# NBT_RTC_ADDON.net
KiCad netlist of a schematic drawn in Altium Designer
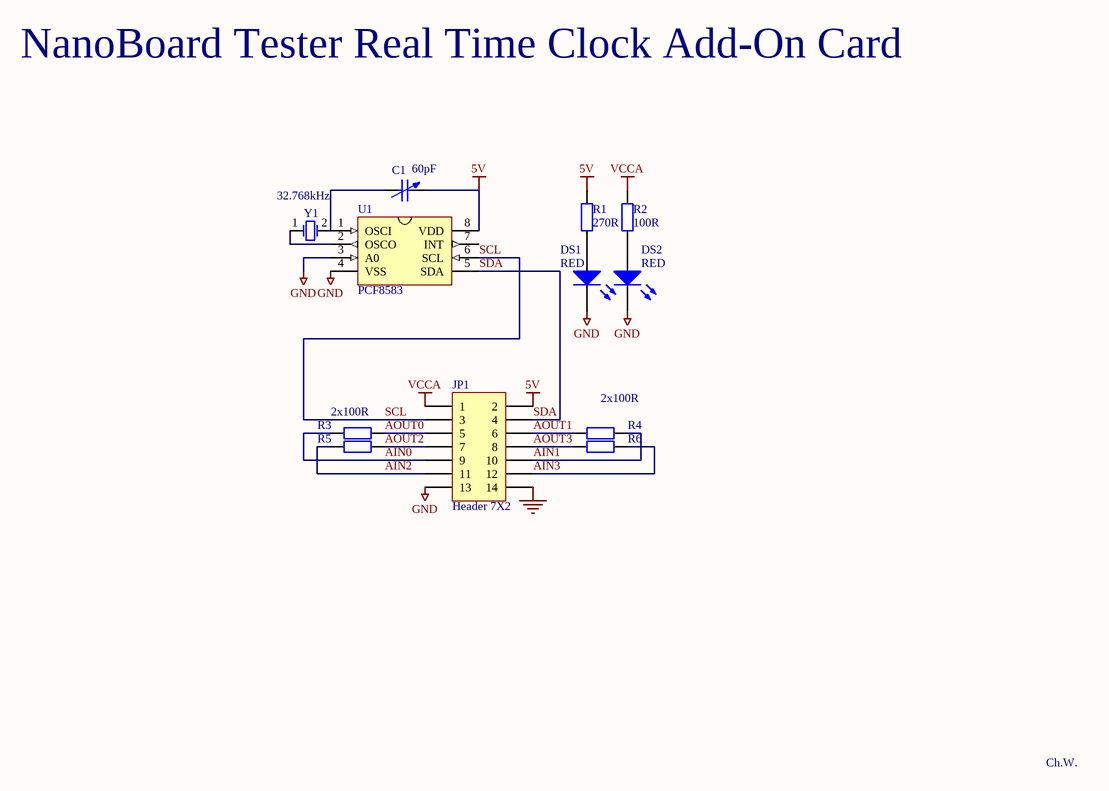
[diagram p0: NBT_RTC_ADDON.SchDoc]

(export (version "E")
  (design (tool "Eeschema 10.0.6"))
  (components
    (comp (ref "C1")
      (value "60pF")
      (footprint "C3225-1210")
      (description "Variable or Adjustable Capacitor")
      (fields
        (field (name "MANUFACTURER") "Generic Components")
        (field (name "Comment") "Cap Var")
        (field (name "PUBLISHER") "Altium Limited")
      )
      (libsource (lib "Miscellaneous Devices") (part "Cap Var"))
    )
    (comp (ref "DS1")
      (value "LED2")
      (footprint "DSO-F2/D6.1")
      (description "Typical RED, GREEN, YELLOW, AMBER GaAs LED")
      (fields
        (field (name "MANUFACTURER") "Generic Components")
        (field (name "ALTIUM_UNNAMED_1") "RED")
        (field (name "PUBLISHER") "Altium Limited")
      )
      (libsource (lib "Miscellaneous Devices") (part "LED2"))
    )
    (comp (ref "DS2")
      (value "LED2")
      (footprint "DSO-F2/D6.1")
      (description "Typical RED, GREEN, YELLOW, AMBER GaAs LED")
      (fields
        (field (name "MANUFACTURER") "Generic Components")
        (field (name "ALTIUM_UNNAMED_1") "RED")
        (field (name "PUBLISHER") "Altium Limited")
      )
      (libsource (lib "Miscellaneous Devices") (part "LED2"))
    )
    (comp (ref "JP1")
      (value "Header 7X2")
      (footprint "HDR2X7")
      (description "Header, 7-Pin, Dual row")
      (fields (field (name "MANUFACTURER") "Generic Components") (field (name "PUBLISHER") "Altium Limited"))
      (libsource (lib "Miscellaneous Connectors") (part "Header 7X2"))
    )
    (comp (ref "R1")
      (value "270R")
      (footprint "AXIAL-0.4")
      (description "Resistor")
      (fields (field (name "MANUFACTURER") "Generic Components") (field (name "PUBLISHER") "Altium Limited"))
      (libsource (lib "") (part "Res2_1"))
    )
    (comp (ref "R2")
      (value "100R")
      (footprint "AXIAL-0.4")
      (description "Resistor")
      (fields (field (name "MANUFACTURER") "Generic Components") (field (name "PUBLISHER") "Altium Limited"))
      (libsource (lib "") (part "Res2_1"))
    )
    (comp (ref "R3")
      (value "Res2")
      (footprint "AXIAL-0.4")
      (description "Resistor")
      (fields (field (name "MANUFACTURER") "Generic Components") (field (name "PUBLISHER") "Altium Limited"))
      (libsource (lib "Miscellaneous Devices") (part "Res2"))
    )
    (comp (ref "R4")
      (value "Res2")
      (footprint "AXIAL-0.4")
      (description "Resistor")
      (fields (field (name "MANUFACTURER") "Generic Components") (field (name "PUBLISHER") "Altium Limited"))
      (libsource (lib "Miscellaneous Devices") (part "Res2"))
    )
    (comp (ref "R5")
      (value "Res2")
      (footprint "AXIAL-0.4")
      (description "Resistor")
      (fields (field (name "MANUFACTURER") "Generic Components") (field (name "PUBLISHER") "Altium Limited"))
      (libsource (lib "Miscellaneous Devices") (part "Res2"))
    )
    (comp (ref "R6")
      (value "Res2")
      (footprint "AXIAL-0.4")
      (description "Resistor")
      (fields (field (name "MANUFACTURER") "Generic Components") (field (name "PUBLISHER") "Altium Limited"))
      (libsource (lib "Miscellaneous Devices") (part "Res2"))
    )
    (comp (ref "U1")
      (value "PCF8583")
      (footprint "DIP-8")
      (description "Clock/Calendar with 240 x 8-bit RAM")
      (libsource (lib "ChrisSchematic") (part "PCF8583"))
    )
    (comp (ref "Y1")
      (value "32.768kHz")
      (footprint "BCY-W2/D3.1")
      (description "Crystal Oscillator")
      (fields (field (name "MANUFACTURER") "Generic Components") (field (name "PUBLISHER") "Altium Limited"))
      (libsource (lib "Miscellaneous Devices") (part "XTAL"))
    )
  )
  (nets
    (net (code "1") (name "/AIN0") (class "Default")
      (node (ref "JP1") (pin "9") (pinfunction "9_9") (pintype "passive"))
      (node (ref "R3") (pin "2") (pinfunction "2_2") (pintype "passive"))
    )
    (net (code "2") (name "/AIN1") (class "Default")
      (node (ref "JP1") (pin "10") (pinfunction "10_10") (pintype "passive"))
      (node (ref "R4") (pin "1") (pinfunction "1_1") (pintype "passive"))
    )
    (net (code "3") (name "/AIN2") (class "Default")
      (node (ref "JP1") (pin "11") (pinfunction "11_11") (pintype "passive"))
      (node (ref "R5") (pin "2") (pinfunction "2_2") (pintype "passive"))
    )
    (net (code "4") (name "/AIN3") (class "Default")
      (node (ref "JP1") (pin "12") (pinfunction "12_12") (pintype "passive"))
      (node (ref "R6") (pin "1") (pinfunction "1_1") (pintype "passive"))
    )
    (net (code "5") (name "/AOUT0") (class "Default")
      (node (ref "JP1") (pin "5") (pinfunction "5_5") (pintype "passive"))
      (node (ref "R3") (pin "1") (pinfunction "1_1") (pintype "passive"))
    )
    (net (code "6") (name "/AOUT1") (class "Default")
      (node (ref "JP1") (pin "6") (pinfunction "6_6") (pintype "passive"))
      (node (ref "R4") (pin "2") (pinfunction "2_2") (pintype "passive"))
    )
    (net (code "7") (name "/AOUT2") (class "Default")
      (node (ref "JP1") (pin "7") (pinfunction "7_7") (pintype "passive"))
      (node (ref "R5") (pin "1") (pinfunction "1_1") (pintype "passive"))
    )
    (net (code "8") (name "/AOUT3") (class "Default")
      (node (ref "JP1") (pin "8") (pinfunction "8_8") (pintype "passive"))
      (node (ref "R6") (pin "2") (pinfunction "2_2") (pintype "passive"))
    )
    (net (code "9") (name "/SCL") (class "Default")
      (node (ref "JP1") (pin "3") (pinfunction "3_3") (pintype "passive"))
      (node (ref "U1") (pin "6") (pinfunction "SCL_6") (pintype "input"))
    )
    (net (code "10") (name "/SDA") (class "Default")
      (node (ref "JP1") (pin "4") (pinfunction "4_4") (pintype "passive"))
      (node (ref "U1") (pin "5") (pinfunction "SDA_5") (pintype "open_collector"))
    )
    (net (code "11") (name "5V") (class "Default")
      (node (ref "C1") (pin "2") (pinfunction "2_2") (pintype "passive"))
      (node (ref "JP1") (pin "2") (pinfunction "2_2") (pintype "passive"))
      (node (ref "R1") (pin "2") (pinfunction "2_2") (pintype "passive"))
      (node (ref "U1") (pin "8") (pinfunction "VDD_8") (pintype "power_in"))
    )
    (net (code "12") (name "GND") (class "Default")
      (node (ref "DS1") (pin "2") (pinfunction "K_2") (pintype "passive"))
      (node (ref "DS2") (pin "2") (pinfunction "K_2") (pintype "passive"))
      (node (ref "JP1") (pin "13") (pinfunction "13_13") (pintype "passive"))
      (node (ref "JP1") (pin "14") (pinfunction "14_14") (pintype "passive"))
      (node (ref "U1") (pin "3") (pinfunction "A0_3") (pintype "input"))
      (node (ref "U1") (pin "4") (pinfunction "VSS_4") (pintype "power_in"))
    )
    (net (code "13") (name "Net-(DS1-A)") (class "Default")
      (node (ref "DS1") (pin "1") (pinfunction "A_1") (pintype "passive"))
      (node (ref "R1") (pin "1") (pinfunction "1_1") (pintype "passive"))
    )
    (net (code "14") (name "Net-(DS2-A)") (class "Default")
      (node (ref "DS2") (pin "1") (pinfunction "A_1") (pintype "passive"))
      (node (ref "R2") (pin "1") (pinfunction "1_1") (pintype "passive"))
    )
    (net (code "15") (name "Net-(U1-OSCI)") (class "Default")
      (node (ref "C1") (pin "1") (pinfunction "1_1") (pintype "passive"))
      (node (ref "U1") (pin "1") (pinfunction "OSCI_1") (pintype "input"))
      (node (ref "Y1") (pin "2") (pinfunction "OSC2_2") (pintype "passive"))
    )
    (net (code "16") (name "Net-(U1-OSCO)") (class "Default")
      (node (ref "U1") (pin "2") (pinfunction "OSCO_2") (pintype "output"))
      (node (ref "Y1") (pin "1") (pinfunction "OSC1_1") (pintype "passive"))
    )
    (net (code "17") (name "VCCA") (class "Default")
      (node (ref "JP1") (pin "1") (pinfunction "1_1") (pintype "passive"))
      (node (ref "R2") (pin "2") (pinfunction "2_2") (pintype "passive"))
    )
    (net (code "18") (name "unconnected-(U1-INT-Pad7)") (class "Default")
      (node (ref "U1") (pin "7") (pinfunction "INT_7") (pintype "output"))
    )
  )
)
